# 9-Protections_1_of_2.net
KiCad netlist of a schematic drawn in Altium Designer
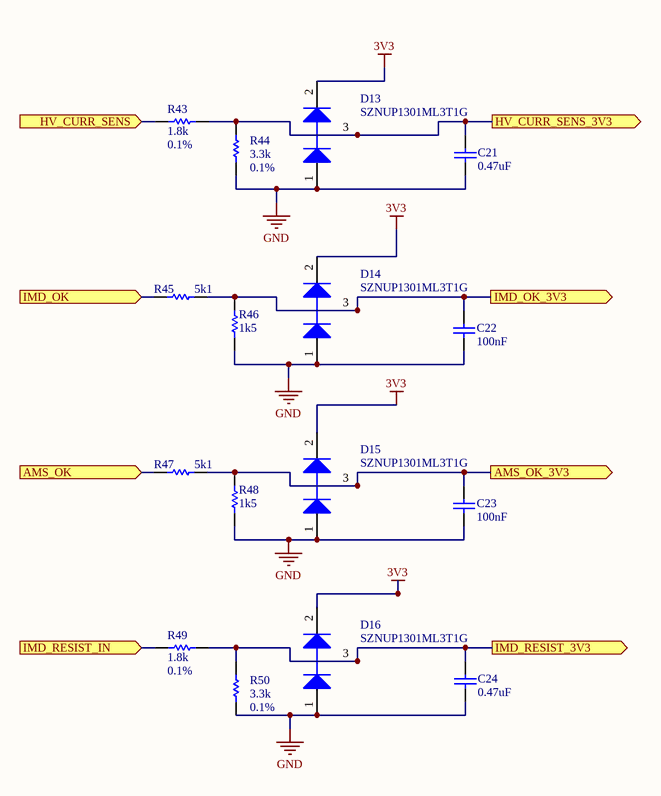
[diagram p0: 9-Protections 1 of 2.SchDoc]

(export (version "E")
  (design (tool "Eeschema 10.0.6"))
  (components
    (comp (ref "C21")
      (value "0.47uF")
      (footprint "1608[0603]")
      (description "Capacitor")
      (fields
        (field (name "MANUFACTURER") "Yageo")
        (field (name "MANUFACTURER PART NUMBER") "CC0603KRX7R8BB474")
      )
      (libsource (lib "Miscellaneous Devices") (part "Cap"))
    )
    (comp (ref "C22")
      (value "100nF")
      (footprint "1608[0603]")
      (description "Capacitor")
      (fields
        (field (name "MANUFACTURER") "Yageo")
        (field (name "MANUFACTURER PART NUMBER") "CC0603KRX7R9BB104")
      )
      (libsource (lib "Miscellaneous Devices") (part "Cap"))
    )
    (comp (ref "C23")
      (value "100nF")
      (footprint "1608[0603]")
      (description "Capacitor")
      (fields
        (field (name "MANUFACTURER") "Yageo")
        (field (name "MANUFACTURER PART NUMBER") "CC0603KRX7R9BB104")
      )
      (libsource (lib "Miscellaneous Devices") (part "Cap"))
    )
    (comp (ref "C24")
      (value "0.47uF")
      (footprint "1608[0603]")
      (description "Capacitor")
      (fields
        (field (name "MANUFACTURER") "Yageo")
        (field (name "MANUFACTURER PART NUMBER") "CC0603KRX7R8BB474")
      )
      (libsource (lib "Miscellaneous Devices") (part "Cap"))
    )
    (comp (ref "D13")
      (value "SZNUP1301ML3T1G")
      (footprint "ONSC-SOT-23-3-318-08_V")
      (fields (field (name "MANUFACTURER") "On Semiconductor"))
      (libsource (lib "Altium Content Vault") (part "ONSC-NUP1301-SOT-23-3-318-08"))
    )
    (comp (ref "D14")
      (value "SZNUP1301ML3T1G")
      (footprint "ONSC-SOT-23-3-318-08_V")
      (fields (field (name "MANUFACTURER") "On Semiconductor"))
      (libsource (lib "Altium Content Vault") (part "ONSC-NUP1301-SOT-23-3-318-08"))
    )
    (comp (ref "D15")
      (value "SZNUP1301ML3T1G")
      (footprint "ONSC-SOT-23-3-318-08_V")
      (fields (field (name "MANUFACTURER") "On Semiconductor"))
      (libsource (lib "Altium Content Vault") (part "ONSC-NUP1301-SOT-23-3-318-08"))
    )
    (comp (ref "D16")
      (value "SZNUP1301ML3T1G")
      (footprint "ONSC-SOT-23-3-318-08_V")
      (fields (field (name "MANUFACTURER") "On Semiconductor"))
      (libsource (lib "Altium Content Vault") (part "ONSC-NUP1301-SOT-23-3-318-08"))
    )
    (comp (ref "R43")
      (value "1.8k")
      (footprint "1608[0603]")
      (description "Resistor")
      (fields
        (field (name "TOLERANCE") "0.1%")
        (field (name "MANUFACTURER") "Panasonic Electronic Components")
        (field (name "MANUFACTURER PART NUMBER") "ERJ-PB6B1801V")
      )
      (libsource (lib "Miscellaneous Devices") (part "Res1"))
    )
    (comp (ref "R44")
      (value "3.3k")
      (footprint "1608[0603]")
      (description "Resistor")
      (fields
        (field (name "TOLERANCE") "0.1%")
        (field (name "MANUFACTURER") "Panasonic Electronic Components")
        (field (name "MANUFACTURER PART NUMBER") "ERJ-PB6B3301V")
      )
      (libsource (lib "Miscellaneous Devices") (part "Res1"))
    )
    (comp (ref "R45")
      (value "5k1")
      (footprint "1608[0603]")
      (description "Resistor")
      (fields
        (field (name "MANUFACTURER") "Yageo")
        (field (name "MANUFACTURER PART NUMBER") "RC0603JR-075K1L")
      )
      (libsource (lib "Miscellaneous Devices") (part "Res1"))
    )
    (comp (ref "R46")
      (value "1k5")
      (footprint "1608[0603]")
      (description "Resistor")
      (fields
        (field (name "MANUFACTURER") "Yageo")
        (field (name "MANUFACTURER PART NUMBER") "RC0603JR-075K1L")
      )
      (libsource (lib "Miscellaneous Devices") (part "Res1"))
    )
    (comp (ref "R47")
      (value "5k1")
      (footprint "1608[0603]")
      (description "Resistor")
      (fields
        (field (name "MANUFACTURER") "Yageo")
        (field (name "MANUFACTURER PART NUMBER") "RC0603JR-075K1L")
      )
      (libsource (lib "Miscellaneous Devices") (part "Res1"))
    )
    (comp (ref "R48")
      (value "1k5")
      (footprint "1608[0603]")
      (description "Resistor")
      (fields
        (field (name "MANUFACTURER") "Yageo")
        (field (name "MANUFACTURER PART NUMBER") "RC0603JR-075K1L")
      )
      (libsource (lib "Miscellaneous Devices") (part "Res1"))
    )
    (comp (ref "R49")
      (value "1.8k")
      (footprint "1608[0603]")
      (description "Resistor")
      (fields
        (field (name "TOLERANCE") "0.1%")
        (field (name "MANUFACTURER") "Panasonic Electronic Components")
        (field (name "MANUFACTURER PART NUMBER") "ERJ-PB6B1801V")
      )
      (libsource (lib "Miscellaneous Devices") (part "Res1"))
    )
    (comp (ref "R50")
      (value "3.3k")
      (footprint "1608[0603]")
      (description "Resistor")
      (fields
        (field (name "TOLERANCE") "0.1%")
        (field (name "MANUFACTURER") "Panasonic Electronic Components")
        (field (name "MANUFACTURER PART NUMBER") "ERJ-PB6B3301V")
      )
      (libsource (lib "Miscellaneous Devices") (part "Res1"))
    )
  )
  (nets
    (net (code "1") (name "/AMS_OK") (class "Default")
      (node (ref "R47") (pin "1") (pinfunction "1_1") (pintype "passive"))
    )
    (net (code "2") (name "/AMS_OK_3V3") (class "Default")
      (node (ref "C23") (pin "2") (pinfunction "2_2") (pintype "passive"))
      (node (ref "D15") (pin "3") (pinfunction "K/A_3") (pintype "passive"))
      (node (ref "R47") (pin "2") (pinfunction "2_2") (pintype "passive"))
      (node (ref "R48") (pin "2") (pinfunction "2_2") (pintype "passive"))
    )
    (net (code "3") (name "/HV_CURR_SENS") (class "Default")
      (node (ref "R43") (pin "2") (pinfunction "2_2") (pintype "passive"))
    )
    (net (code "4") (name "/HV_CURR_SENS_3V3") (class "Default")
      (node (ref "C21") (pin "2") (pinfunction "2_2") (pintype "passive"))
      (node (ref "D13") (pin "3") (pinfunction "K/A_3") (pintype "passive"))
      (node (ref "R43") (pin "1") (pinfunction "1_1") (pintype "passive"))
      (node (ref "R44") (pin "2") (pinfunction "2_2") (pintype "passive"))
    )
    (net (code "5") (name "/IMD_OK") (class "Default")
      (node (ref "R45") (pin "1") (pinfunction "1_1") (pintype "passive"))
    )
    (net (code "6") (name "/IMD_OK_3V3") (class "Default")
      (node (ref "C22") (pin "2") (pinfunction "2_2") (pintype "passive"))
      (node (ref "D14") (pin "3") (pinfunction "K/A_3") (pintype "passive"))
      (node (ref "R45") (pin "2") (pinfunction "2_2") (pintype "passive"))
      (node (ref "R46") (pin "2") (pinfunction "2_2") (pintype "passive"))
    )
    (net (code "7") (name "/IMD_RESIST_3V3") (class "Default")
      (node (ref "C24") (pin "2") (pinfunction "2_2") (pintype "passive"))
      (node (ref "D16") (pin "3") (pinfunction "K/A_3") (pintype "passive"))
      (node (ref "R49") (pin "1") (pinfunction "1_1") (pintype "passive"))
      (node (ref "R50") (pin "2") (pinfunction "2_2") (pintype "passive"))
    )
    (net (code "8") (name "/IMD_RESIST_IN") (class "Default")
      (node (ref "R49") (pin "2") (pinfunction "2_2") (pintype "passive"))
    )
    (net (code "9") (name "3V3") (class "Default")
      (node (ref "D13") (pin "2") (pinfunction "K_2") (pintype "passive"))
      (node (ref "D14") (pin "2") (pinfunction "K_2") (pintype "passive"))
      (node (ref "D15") (pin "2") (pinfunction "K_2") (pintype "passive"))
      (node (ref "D16") (pin "2") (pinfunction "K_2") (pintype "passive"))
    )
    (net (code "10") (name "GND") (class "Default")
      (node (ref "C21") (pin "1") (pinfunction "1_1") (pintype "passive"))
      (node (ref "C22") (pin "1") (pinfunction "1_1") (pintype "passive"))
      (node (ref "C23") (pin "1") (pinfunction "1_1") (pintype "passive"))
      (node (ref "C24") (pin "1") (pinfunction "1_1") (pintype "passive"))
      (node (ref "D13") (pin "1") (pinfunction "A_1") (pintype "passive"))
      (node (ref "D14") (pin "1") (pinfunction "A_1") (pintype "passive"))
      (node (ref "D15") (pin "1") (pinfunction "A_1") (pintype "passive"))
      (node (ref "D16") (pin "1") (pinfunction "A_1") (pintype "passive"))
      (node (ref "R44") (pin "1") (pinfunction "1_1") (pintype "passive"))
      (node (ref "R46") (pin "1") (pinfunction "1_1") (pintype "passive"))
      (node (ref "R48") (pin "1") (pinfunction "1_1") (pintype "passive"))
      (node (ref "R50") (pin "1") (pinfunction "1_1") (pintype "passive"))
    )
  )
)
